# USB-C.net
KiCad netlist of a schematic drawn in EAGLE
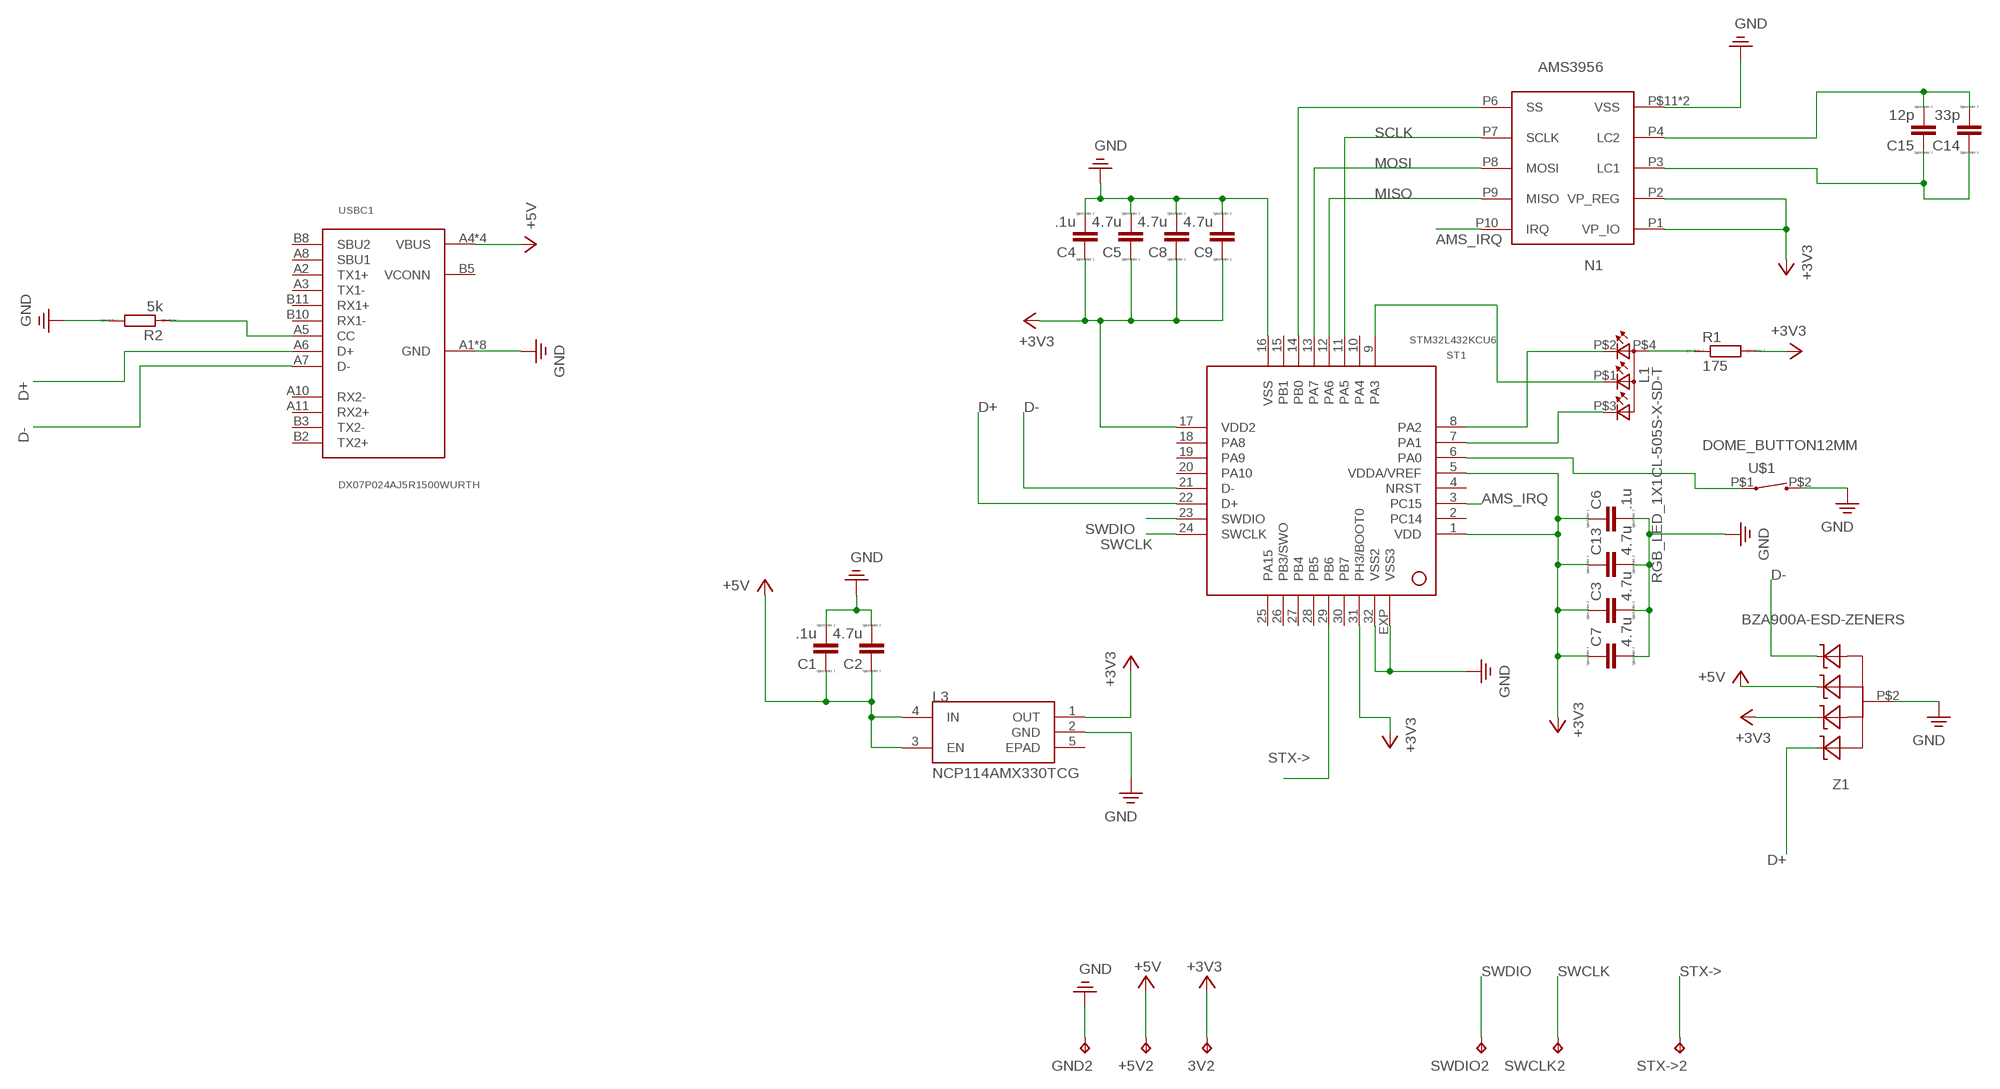
[diagram p0: schematic, sheet 1]

(export (version "E")
  (design (tool "Eeschema 10.0.6"))
  (components
    (comp (ref "+5V2")
      (value "TEST_POINT")
      (footprint "eagle-import:B1,27")
      (libsource (lib "eagle-import") (part "TEST_POINT"))
    )
    (comp (ref "3V2")
      (value "TEST_POINT")
      (footprint "eagle-import:B1,27")
      (libsource (lib "eagle-import") (part "TEST_POINT"))
    )
    (comp (ref "C1")
      (value ".1u")
      (footprint "eagle-import:C0402")
      (libsource (lib "eagle-import") (part "CAPACITOR"))
    )
    (comp (ref "C2")
      (value "4.7u")
      (footprint "eagle-import:C0402")
      (libsource (lib "eagle-import") (part "CAPACITOR"))
    )
    (comp (ref "C3")
      (value "4.7u")
      (footprint "eagle-import:C0402")
      (libsource (lib "eagle-import") (part "CAPACITOR"))
    )
    (comp (ref "C4")
      (value ".1u")
      (footprint "eagle-import:C0402")
      (libsource (lib "eagle-import") (part "CAPACITOR"))
    )
    (comp (ref "C5")
      (value "4.7u")
      (footprint "eagle-import:C0402")
      (libsource (lib "eagle-import") (part "CAPACITOR"))
    )
    (comp (ref "C6")
      (value ".1u")
      (footprint "eagle-import:C0402")
      (libsource (lib "eagle-import") (part "CAPACITOR"))
    )
    (comp (ref "C7")
      (value "4.7u")
      (footprint "eagle-import:C0402")
      (libsource (lib "eagle-import") (part "CAPACITOR"))
    )
    (comp (ref "C8")
      (value "4.7u")
      (footprint "eagle-import:C0402")
      (libsource (lib "eagle-import") (part "CAPACITOR"))
    )
    (comp (ref "C9")
      (value "4.7u")
      (footprint "eagle-import:C0402")
      (libsource (lib "eagle-import") (part "CAPACITOR"))
    )
    (comp (ref "C13")
      (value "4.7u")
      (footprint "eagle-import:C0402")
      (libsource (lib "eagle-import") (part "CAPACITOR"))
    )
    (comp (ref "C14")
      (value "33p")
      (footprint "eagle-import:C0402")
      (libsource (lib "eagle-import") (part "CAPACITOR"))
    )
    (comp (ref "C15")
      (value "12p")
      (footprint "eagle-import:C0402")
      (libsource (lib "eagle-import") (part "CAPACITOR"))
    )
    (comp (ref "GND2")
      (value "TEST_POINT")
      (footprint "eagle-import:B1,27")
      (libsource (lib "eagle-import") (part "TEST_POINT"))
    )
    (comp (ref "L1")
      (value "RGB_LED_1X1CL-505S-X-SD-T")
      (footprint "eagle-import:CL-505S-X-SD-T")
      (libsource (lib "eagle-import") (part "RGB_LED_1X1CL-505S-X-SD-T"))
    )
    (comp (ref "L3")
      (value "NCP114AMX330TCG")
      (footprint "eagle-import:REG_NCP114AMX330TCG")
      (fields (field (name "MF") "ON Semiconductor"))
      (libsource (lib "eagle-import") (part "NCP114AMX330TCG"))
    )
    (comp (ref "N1")
      (value "AMS3956")
      (footprint "eagle-import:MLPD3X3")
      (libsource (lib "eagle-import") (part "AMS3956"))
    )
    (comp (ref "R1")
      (value "175")
      (footprint "eagle-import:R0402")
      (libsource (lib "eagle-import") (part "RESISTOR"))
    )
    (comp (ref "R2")
      (value "5k")
      (footprint "eagle-import:R0402")
      (libsource (lib "eagle-import") (part "RESISTOR"))
    )
    (comp (ref "ST1")
      (value "STM32L432KCU6")
      (footprint "eagle-import:QFN32")
      (libsource (lib "eagle-import") (part "STM32L432KCU6"))
    )
    (comp (ref "STX->2")
      (value "TEST_POINT")
      (footprint "eagle-import:B1,27")
      (libsource (lib "eagle-import") (part "TEST_POINT"))
    )
    (comp (ref "SWCLK2")
      (value "TEST_POINT")
      (footprint "eagle-import:B1,27")
      (libsource (lib "eagle-import") (part "TEST_POINT"))
    )
    (comp (ref "SWDIO2")
      (value "TEST_POINT")
      (footprint "eagle-import:B1,27")
      (libsource (lib "eagle-import") (part "TEST_POINT"))
    )
    (comp (ref "U$1")
      (value "DOME_BUTTON12MM")
      (footprint "eagle-import:DOME-BL-12MM")
      (libsource (lib "eagle-import") (part "DOME_BUTTON12MM"))
    )
    (comp (ref "USBC1")
      (value "DX07P024AJ5R1500WURTH")
      (footprint "eagle-import:WüRTH_632712000112")
      (libsource (lib "eagle-import") (part "DX07P024AJ5R1500WURTH"))
    )
    (comp (ref "Z1")
      (value "BZA900A-ESD-ZENERS")
      (footprint "eagle-import:BZA900A")
      (libsource (lib "eagle-import") (part "BZA900A-ESD-ZENERS"))
    )
  )
  (nets
    (net (code "1") (name "+3V3") (class "Default")
      (node (ref "3V2") (pin "TP") (pinfunction "TP_TP") (pintype "input"))
      (node (ref "C13") (pin "1") (pinfunction "1_1") (pintype "passive"))
      (node (ref "C3") (pin "1") (pinfunction "1_1") (pintype "passive"))
      (node (ref "C4") (pin "1") (pinfunction "1_1") (pintype "passive"))
      (node (ref "C5") (pin "1") (pinfunction "1_1") (pintype "passive"))
      (node (ref "C6") (pin "1") (pinfunction "1_1") (pintype "passive"))
      (node (ref "C7") (pin "1") (pinfunction "1_1") (pintype "passive"))
      (node (ref "C8") (pin "1") (pinfunction "1_1") (pintype "passive"))
      (node (ref "C9") (pin "1") (pinfunction "1_1") (pintype "passive"))
      (node (ref "L3") (pin "1") (pinfunction "OUT_1") (pintype "output"))
      (node (ref "N1") (pin "P1") (pinfunction "VP_IO_P1") (pintype "bidirectional"))
      (node (ref "N1") (pin "P2") (pinfunction "VP_REG_P2") (pintype "bidirectional"))
      (node (ref "R1") (pin "2") (pinfunction "2_2") (pintype "passive"))
      (node (ref "ST1") (pin "1") (pinfunction "VDD_1") (pintype "bidirectional"))
      (node (ref "ST1") (pin "17") (pinfunction "VDD2_17") (pintype "bidirectional"))
      (node (ref "ST1") (pin "31") (pinfunction "PH3/BOOT0_31") (pintype "bidirectional"))
      (node (ref "ST1") (pin "5") (pinfunction "VDDA/VREF_5") (pintype "bidirectional"))
      (node (ref "Z1") (pin "P$5") (pinfunction "C1_P$5") (pintype "passive"))
    )
    (net (code "2") (name "+5V") (class "Default")
      (node (ref "+5V2") (pin "TP") (pinfunction "TP_TP") (pintype "input"))
      (node (ref "C1") (pin "1") (pinfunction "1_1") (pintype "passive"))
      (node (ref "C2") (pin "1") (pinfunction "1_1") (pintype "passive"))
      (node (ref "L3") (pin "3") (pinfunction "EN_3") (pintype "input"))
      (node (ref "L3") (pin "4") (pinfunction "IN_4") (pintype "input"))
      (node (ref "USBC1") (pin "A4") (pinfunction "VBUS_A4") (pintype "bidirectional"))
      (node (ref "USBC1") (pin "A9") (pinfunction "VBUS_A9") (pintype "bidirectional"))
      (node (ref "USBC1") (pin "B4") (pinfunction "VBUS_B4") (pintype "bidirectional"))
      (node (ref "USBC1") (pin "B9") (pinfunction "VBUS_B9") (pintype "bidirectional"))
      (node (ref "Z1") (pin "P$1") (pinfunction "C_P$1") (pintype "passive"))
    )
    (net (code "3") (name "/AMS_IRQ") (class "Default")
      (node (ref "N1") (pin "P10") (pinfunction "IRQ_P10") (pintype "bidirectional"))
      (node (ref "ST1") (pin "3") (pinfunction "PC15_3") (pintype "bidirectional"))
    )
    (net (code "4") (name "/D+") (class "Default")
      (node (ref "ST1") (pin "22") (pinfunction "D+_22") (pintype "bidirectional"))
      (node (ref "USBC1") (pin "A6") (pinfunction "D+_A6") (pintype "bidirectional"))
      (node (ref "Z1") (pin "P$3") (pinfunction "C3_P$3") (pintype "passive"))
    )
    (net (code "5") (name "/D-") (class "Default")
      (node (ref "ST1") (pin "21") (pinfunction "D-_21") (pintype "bidirectional"))
      (node (ref "USBC1") (pin "A7") (pinfunction "D-_A7") (pintype "bidirectional"))
      (node (ref "Z1") (pin "P$4") (pinfunction "C2_P$4") (pintype "passive"))
    )
    (net (code "6") (name "/MISO") (class "Default")
      (node (ref "N1") (pin "P9") (pinfunction "MISO_P9") (pintype "bidirectional"))
      (node (ref "ST1") (pin "12") (pinfunction "PA6_12") (pintype "bidirectional"))
    )
    (net (code "7") (name "/MOSI") (class "Default")
      (node (ref "N1") (pin "P8") (pinfunction "MOSI_P8") (pintype "bidirectional"))
      (node (ref "ST1") (pin "13") (pinfunction "PA7_13") (pintype "bidirectional"))
    )
    (net (code "8") (name "/SCLK") (class "Default")
      (node (ref "N1") (pin "P7") (pinfunction "SCLK_P7") (pintype "bidirectional"))
      (node (ref "ST1") (pin "11") (pinfunction "PA5_11") (pintype "bidirectional"))
    )
    (net (code "9") (name "/STX->") (class "Default")
      (node (ref "ST1") (pin "29") (pinfunction "PB6_29") (pintype "bidirectional"))
      (node (ref "STX->2") (pin "TP") (pinfunction "TP_TP") (pintype "input"))
    )
    (net (code "10") (name "/SWCLK") (class "Default")
      (node (ref "ST1") (pin "24") (pinfunction "SWCLK_24") (pintype "bidirectional"))
      (node (ref "SWCLK2") (pin "TP") (pinfunction "TP_TP") (pintype "input"))
    )
    (net (code "11") (name "/SWDIO") (class "Default")
      (node (ref "ST1") (pin "23") (pinfunction "SWDIO_23") (pintype "bidirectional"))
      (node (ref "SWDIO2") (pin "TP") (pinfunction "TP_TP") (pintype "input"))
    )
    (net (code "12") (name "GND") (class "Default")
      (node (ref "C1") (pin "2") (pinfunction "2_2") (pintype "passive"))
      (node (ref "C13") (pin "2") (pinfunction "2_2") (pintype "passive"))
      (node (ref "C2") (pin "2") (pinfunction "2_2") (pintype "passive"))
      (node (ref "C3") (pin "2") (pinfunction "2_2") (pintype "passive"))
      (node (ref "C4") (pin "2") (pinfunction "2_2") (pintype "passive"))
      (node (ref "C5") (pin "2") (pinfunction "2_2") (pintype "passive"))
      (node (ref "C6") (pin "2") (pinfunction "2_2") (pintype "passive"))
      (node (ref "C7") (pin "2") (pinfunction "2_2") (pintype "passive"))
      (node (ref "C8") (pin "2") (pinfunction "2_2") (pintype "passive"))
      (node (ref "C9") (pin "2") (pinfunction "2_2") (pintype "passive"))
      (node (ref "GND2") (pin "TP") (pinfunction "TP_TP") (pintype "input"))
      (node (ref "L3") (pin "2") (pinfunction "GND_2") (pintype "power_in"))
      (node (ref "N1") (pin "P$11") (pinfunction "VSS_P$11") (pintype "bidirectional"))
      (node (ref "N1") (pin "P5") (pinfunction "VSS_P5") (pintype "bidirectional"))
      (node (ref "R2") (pin "2") (pinfunction "2_2") (pintype "passive"))
      (node (ref "ST1") (pin "16") (pinfunction "VSS_16") (pintype "bidirectional"))
      (node (ref "ST1") (pin "32") (pinfunction "VSS2_32") (pintype "bidirectional"))
      (node (ref "ST1") (pin "EXP") (pinfunction "VSS3_EXP") (pintype "bidirectional"))
      (node (ref "U$1") (pin "P$2") (pinfunction "2_P$2") (pintype "passive"))
      (node (ref "USBC1") (pin "A1") (pinfunction "GND_A1") (pintype "bidirectional"))
      (node (ref "USBC1") (pin "A12") (pinfunction "GND_A12") (pintype "bidirectional"))
      (node (ref "USBC1") (pin "B1") (pinfunction "GND_B1") (pintype "bidirectional"))
      (node (ref "USBC1") (pin "B12") (pinfunction "GND_B12") (pintype "bidirectional"))
      (node (ref "USBC1") (pin "P_GND1") (pinfunction "GND_P_GND1") (pintype "bidirectional"))
      (node (ref "USBC1") (pin "P_GND2") (pinfunction "GND_P_GND2") (pintype "bidirectional"))
      (node (ref "USBC1") (pin "P_GND3") (pinfunction "GND_P_GND3") (pintype "bidirectional"))
      (node (ref "USBC1") (pin "P_GND4") (pinfunction "GND_P_GND4") (pintype "bidirectional"))
      (node (ref "Z1") (pin "P$2") (pinfunction "P$1_P$2") (pintype "bidirectional"))
    )
    (net (code "13") (name "Net-(L1-A2)") (class "Default")
      (node (ref "L1") (pin "P$4") (pinfunction "A2_P$4") (pintype "passive"))
      (node (ref "R1") (pin "1") (pinfunction "1_1") (pintype "passive"))
    )
    (net (code "14") (name "Net-(L1-CBLUE)") (class "Default")
      (node (ref "L1") (pin "P$1") (pinfunction "CBLUE_P$1") (pintype "passive"))
      (node (ref "ST1") (pin "9") (pinfunction "PA3_9") (pintype "bidirectional"))
    )
    (net (code "15") (name "Net-(L1-CGREEN)") (class "Default")
      (node (ref "L1") (pin "P$3") (pinfunction "CGREEN_P$3") (pintype "passive"))
      (node (ref "ST1") (pin "7") (pinfunction "PA1_7") (pintype "bidirectional"))
    )
    (net (code "16") (name "Net-(L1-CRED)") (class "Default")
      (node (ref "L1") (pin "P$2") (pinfunction "CRED_P$2") (pintype "passive"))
      (node (ref "ST1") (pin "8") (pinfunction "PA2_8") (pintype "bidirectional"))
    )
    (net (code "17") (name "Net-(N1-LC1)") (class "Default")
      (node (ref "C14") (pin "1") (pinfunction "1_1") (pintype "passive"))
      (node (ref "C15") (pin "1") (pinfunction "1_1") (pintype "passive"))
      (node (ref "N1") (pin "P3") (pinfunction "LC1_P3") (pintype "bidirectional"))
    )
    (net (code "18") (name "Net-(N1-LC2)") (class "Default")
      (node (ref "C14") (pin "2") (pinfunction "2_2") (pintype "passive"))
      (node (ref "C15") (pin "2") (pinfunction "2_2") (pintype "passive"))
      (node (ref "N1") (pin "P4") (pinfunction "LC2_P4") (pintype "bidirectional"))
    )
    (net (code "19") (name "Net-(N1-SS)") (class "Default")
      (node (ref "N1") (pin "P6") (pinfunction "SS_P6") (pintype "bidirectional"))
      (node (ref "ST1") (pin "14") (pinfunction "PB0_14") (pintype "bidirectional"))
    )
    (net (code "20") (name "Net-(ST1-PA0)") (class "Default")
      (node (ref "ST1") (pin "6") (pinfunction "PA0_6") (pintype "bidirectional"))
      (node (ref "U$1") (pin "P$1") (pinfunction "1_P$1") (pintype "passive"))
    )
    (net (code "21") (name "Net-(USBC1-CC)") (class "Default")
      (node (ref "R2") (pin "1") (pinfunction "1_1") (pintype "passive"))
      (node (ref "USBC1") (pin "A5") (pinfunction "CC_A5") (pintype "bidirectional"))
    )
    (net (code "22") (name "unconnected-(L3-EPAD-Pad5)") (class "Default")
      (node (ref "L3") (pin "5") (pinfunction "EPAD_5") (pintype "passive"))
    )
    (net (code "23") (name "unconnected-(ST1-NRST-Pad4)") (class "Default")
      (node (ref "ST1") (pin "4") (pinfunction "NRST_4") (pintype "bidirectional"))
    )
    (net (code "24") (name "unconnected-(ST1-PA4-Pad10)") (class "Default")
      (node (ref "ST1") (pin "10") (pinfunction "PA4_10") (pintype "bidirectional"))
    )
    (net (code "25") (name "unconnected-(ST1-PA8-Pad18)") (class "Default")
      (node (ref "ST1") (pin "18") (pinfunction "PA8_18") (pintype "bidirectional"))
    )
    (net (code "26") (name "unconnected-(ST1-PA9-Pad19)") (class "Default")
      (node (ref "ST1") (pin "19") (pinfunction "PA9_19") (pintype "bidirectional"))
    )
    (net (code "27") (name "unconnected-(ST1-PA10-Pad20)") (class "Default")
      (node (ref "ST1") (pin "20") (pinfunction "PA10_20") (pintype "bidirectional"))
    )
    (net (code "28") (name "unconnected-(ST1-PA15-Pad25)") (class "Default")
      (node (ref "ST1") (pin "25") (pinfunction "PA15_25") (pintype "bidirectional"))
    )
    (net (code "29") (name "unconnected-(ST1-PB1-Pad15)") (class "Default")
      (node (ref "ST1") (pin "15") (pinfunction "PB1_15") (pintype "bidirectional"))
    )
    (net (code "30") (name "unconnected-(ST1-PB3{slash}SWO-Pad26)") (class "Default")
      (node (ref "ST1") (pin "26") (pinfunction "PB3/SWO_26") (pintype "bidirectional"))
    )
    (net (code "31") (name "unconnected-(ST1-PB4-Pad27)") (class "Default")
      (node (ref "ST1") (pin "27") (pinfunction "PB4_27") (pintype "bidirectional"))
    )
    (net (code "32") (name "unconnected-(ST1-PB5-Pad28)") (class "Default")
      (node (ref "ST1") (pin "28") (pinfunction "PB5_28") (pintype "bidirectional"))
    )
    (net (code "33") (name "unconnected-(ST1-PB7-Pad30)") (class "Default")
      (node (ref "ST1") (pin "30") (pinfunction "PB7_30") (pintype "bidirectional"))
    )
    (net (code "34") (name "unconnected-(ST1-PC14-Pad2)") (class "Default")
      (node (ref "ST1") (pin "2") (pinfunction "PC14_2") (pintype "bidirectional"))
    )
    (net (code "35") (name "unconnected-(USBC1-RX1+-PadB11)") (class "Default")
      (node (ref "USBC1") (pin "B11") (pinfunction "RX1+_B11") (pintype "bidirectional"))
    )
    (net (code "36") (name "unconnected-(USBC1-RX1--PadB10)") (class "Default")
      (node (ref "USBC1") (pin "B10") (pinfunction "RX1-_B10") (pintype "bidirectional"))
    )
    (net (code "37") (name "unconnected-(USBC1-RX2+-PadA11)") (class "Default")
      (node (ref "USBC1") (pin "A11") (pinfunction "RX2+_A11") (pintype "bidirectional"))
    )
    (net (code "38") (name "unconnected-(USBC1-RX2--PadA10)") (class "Default")
      (node (ref "USBC1") (pin "A10") (pinfunction "RX2-_A10") (pintype "bidirectional"))
    )
    (net (code "39") (name "unconnected-(USBC1-SBU1-PadA8)") (class "Default")
      (node (ref "USBC1") (pin "A8") (pinfunction "SBU1_A8") (pintype "bidirectional"))
    )
    (net (code "40") (name "unconnected-(USBC1-SBU2-PadB8)") (class "Default")
      (node (ref "USBC1") (pin "B8") (pinfunction "SBU2_B8") (pintype "bidirectional"))
    )
    (net (code "41") (name "unconnected-(USBC1-TX1+-PadA2)") (class "Default")
      (node (ref "USBC1") (pin "A2") (pinfunction "TX1+_A2") (pintype "bidirectional"))
    )
    (net (code "42") (name "unconnected-(USBC1-TX1--PadA3)") (class "Default")
      (node (ref "USBC1") (pin "A3") (pinfunction "TX1-_A3") (pintype "bidirectional"))
    )
    (net (code "43") (name "unconnected-(USBC1-TX2+-PadB2)") (class "Default")
      (node (ref "USBC1") (pin "B2") (pinfunction "TX2+_B2") (pintype "bidirectional"))
    )
    (net (code "44") (name "unconnected-(USBC1-TX2--PadB3)") (class "Default")
      (node (ref "USBC1") (pin "B3") (pinfunction "TX2-_B3") (pintype "bidirectional"))
    )
    (net (code "45") (name "unconnected-(USBC1-VCONN-PadB5)") (class "Default")
      (node (ref "USBC1") (pin "B5") (pinfunction "VCONN_B5") (pintype "bidirectional"))
    )
  )
)
